# Sheet1.net
KiCad netlist of a schematic drawn in Altium Designer
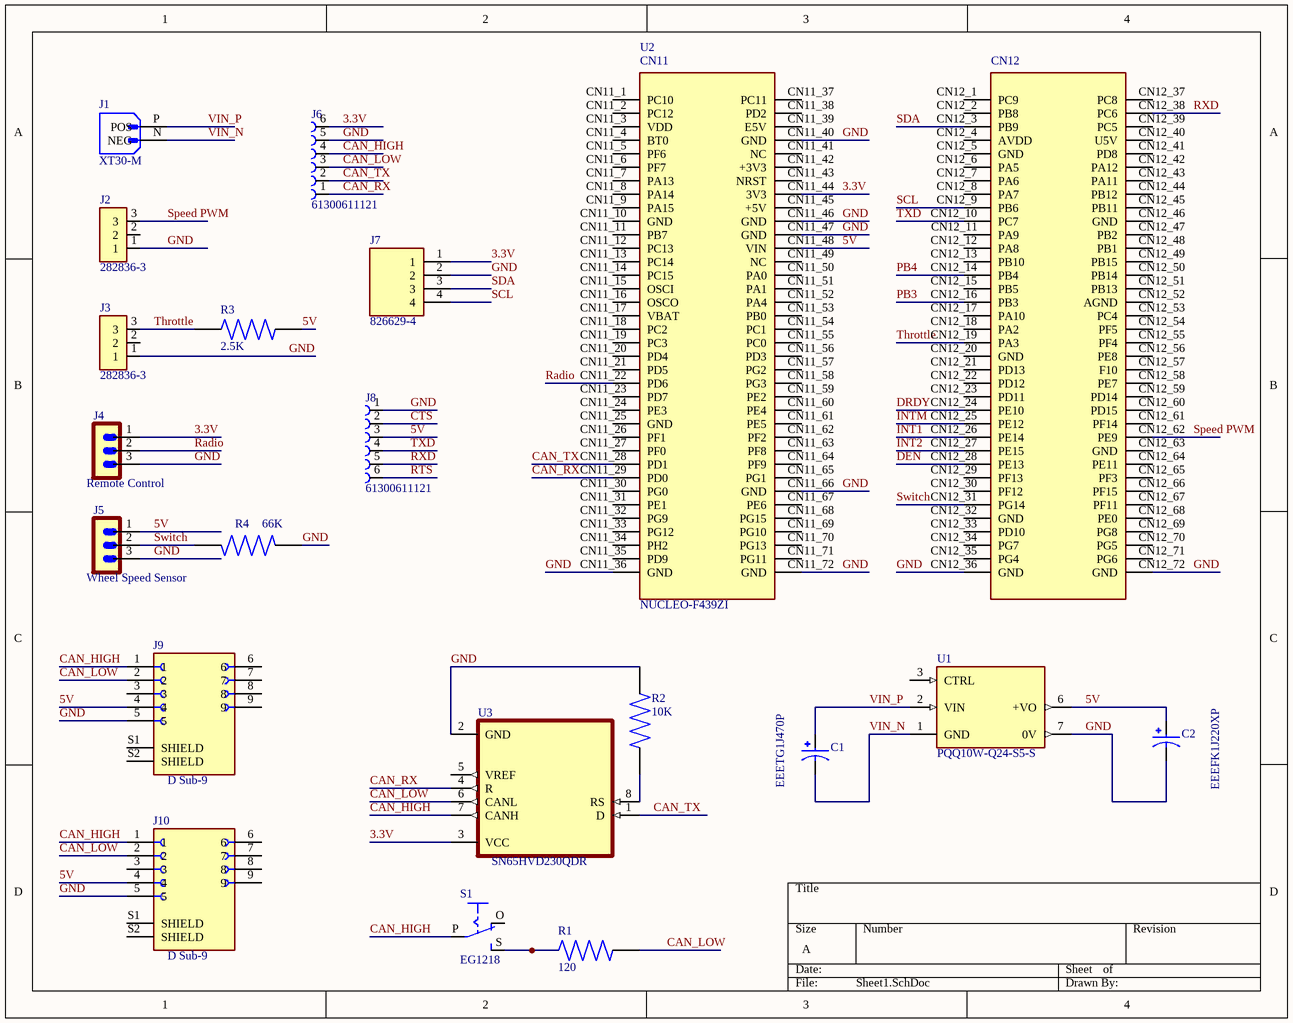
[diagram p0: Sheet1.SchDoc]

(export (version "E")
  (design (tool "Eeschema 10.0.6"))
  (components
    (comp (ref "C1")
      (value "EEETG1J470P")
      (footprint "CAP_EEETG1J470P")
      (description "Cap Aluminum 47uF 63V 20% (10 X 10.2mm) SMD 0.8 Ohm 150mA 2000 hr 125Â°C T/R")
      (fields (field (name "MF") "Panasonic Electronic") (field (name "MP") "EEE-TG1J470P"))
      (libsource (lib "EEETG1J470P") (part "EEETG1J470P"))
    )
    (comp (ref "C2")
      (value "EEEFK1J220XP")
      (footprint "CAP_EEEFK1J220XP")
      (description "22ÂµF 63V Aluminum Electrolytic Capacitors Radial, Can - SMD 2000 Hrs @ 105Â°C")
      (fields (field (name "MP") "EEE-FK1J220XP") (field (name "MF") "Panasonic"))
      (libsource (lib "EEEFK1J220XP") (part "EEEFK1J220XP"))
    )
    (comp (ref "J1")
      (value "XT30-M")
      (footprint "AMASS_XT60-M")
      (description "Plug; DC supply; XT60; male; PIN: 2; for cable; soldered; 30A; 500V")
      (fields (field (name "MP") "XT60-M") (field (name "MF") "AMASS"))
      (libsource (lib "XT30-M") (part "XT30-M"))
    )
    (comp (ref "J2")
      (value "282836-3")
      (footprint "TE_282836-3")
      (description "TERM BLOCK 3POS SIDE ENTRY 5MM")
      (libsource (lib "282836-3") (part "282836-3"))
    )
    (comp (ref "J3")
      (value "282836-3")
      (footprint "TE_282836-3")
      (description "TERM BLOCK 3POS SIDE ENTRY 5MM")
      (libsource (lib "282836-3") (part "282836-3"))
    )
    (comp (ref "J4")
      (value "Remote Control")
      (footprint "B3B-PH-K")
      (description "Connector Header Through Hole 3 position 0.079 (2.00mm)")
      (fields (field (name "MP") "B3B-PH-K") (field (name "MF") "JST"))
      (libsource (lib "B3B-PH-K") (part "B3B-PH-K"))
    )
    (comp (ref "J5")
      (value "Wheel Speed Sensor")
      (footprint "B3B-PH-K")
      (description "Connector Header Through Hole 3 position 0.079 (2.00mm)")
      (fields (field (name "MP") "B3B-PH-K") (field (name "MF") "JST"))
      (libsource (lib "B3B-PH-K") (part "B3B-PH-K"))
    )
    (comp (ref "J6")
      (value "61300611121")
      (footprint "61300611121")
      (description "Connector Header Through Hole 6 position 0.100 (2.54mm)")
      (fields (field (name "MF") "WÃ¼rth Elektronik"))
      (libsource (lib "61300611121") (part "61300611121"))
    )
    (comp (ref "J7")
      (value "826629-4")
      (footprint "TE_826629-4")
      (description "Conn Unshrouded Header HDR 4 POS 2.54mm Solder ST Thru-Hole Automotive Carton")
      (fields (field (name "MF") "TE Connectivity"))
      (libsource (lib "826629-4") (part "826629-4"))
    )
    (comp (ref "J8")
      (value "61300611121")
      (footprint "61300611121")
      (description "Connector Header Through Hole 6 position 0.100 (2.54mm)")
      (fields (field (name "MF") "WÃ¼rth Elektronik"))
      (libsource (lib "") (part "61300611121_1"))
    )
    (comp (ref "J9")
      (value "D Sub-9")
      (footprint "ASSMANN_A-DF_09_A_KG-T2S")
      (description "9 Position D-Sub Receptacle, Female Sockets Connector")
      (fields (field (name "MF") "Assmann WSW") (field (name "MP") "A-DF 09 A/KG-T2S"))
      (libsource (lib "A-DF_09_A_KG-T2S") (part "A-DF_09_A_KG-T2S"))
    )
    (comp (ref "J10")
      (value "D Sub-9")
      (footprint "ASSMANN_A-DF_09_A_KG-T2S")
      (description "9 Position D-Sub Receptacle, Female Sockets Connector")
      (fields (field (name "MF") "Assmann WSW") (field (name "MP") "A-DF 09 A/KG-T2S"))
      (libsource (lib "A-DF_09_A_KG-T2S") (part "A-DF_09_A_KG-T2S"))
    )
    (comp (ref "R1")
      (value "120")
      (footprint "RESC3216X65N")
      (fields (field (name "MP") "KTR18EZPF9530"))
      (libsource (lib "KTR18EZPF9530") (part "KTR18EZPF9530"))
    )
    (comp (ref "R2")
      (value "10K")
      (footprint "RESC3216X65N")
      (fields (field (name "MP") "KTR18EZPF9530"))
      (libsource (lib "KTR18EZPF9530") (part "KTR18EZPF9530"))
    )
    (comp (ref "R3")
      (value "2.5K")
      (footprint "RESC3216X65N")
      (fields (field (name "MP") "KTR18EZPF9530"))
      (libsource (lib "KTR18EZPF9530") (part "KTR18EZPF9530"))
    )
    (comp (ref "R4")
      (value "66K")
      (footprint "RESC3216X65N")
      (fields (field (name "MP") "KTR18EZPF9530"))
      (libsource (lib "KTR18EZPF9530") (part "KTR18EZPF9530"))
    )
    (comp (ref "S1") (value "EG1218") (footprint "EG1218:EG1218") (libsource (lib "EG1218") (part "EG1218")))
    (comp (ref "U1")
      (value "PQQ10W-Q24-S5-S")
      (footprint "CONV_PQQ10W-Q24-S5-S")
      (description "10 W, 4:1 Input Range, Single Regulated Output, SIP8, 1500 Vdc Isolation, Dc-Dc Converter")
      (fields (field (name "MF") "CUI Inc."))
      (libsource (lib "PQQ10W-Q24-S5-S") (part "PQQ10W-Q24-S5-S"))
    )
    (comp (ref "U2")
      (value "NUCLEO-F439ZI")
      (footprint "Nucleo-F439ZI")
      (fields (field (name "MP") "NUCLEO-F429ZI"))
      (libsource (lib "Nucleo-F439ZI") (part "NUCLEO-F439ZI"))
    )
    (comp (ref "U3")
      (value "SN65HVD230QDR")
      (footprint "SOIC127P599X175-8N")
      (description "3.3-V CAN Transceiver with Standby Mode 8-SOIC -40 to 125")
      (fields (field (name "MF") "Texas Instruments"))
      (libsource (lib "SN65HVD230QDR") (part "SN65HVD230QDR"))
    )
  )
  (nets
    (net (code "1") (name "/3.3V") (class "Default")
      (node (ref "J4") (pin "1") (pinfunction "1_1") (pintype "passive"))
      (node (ref "J6") (pin "6") (pinfunction "6_6") (pintype "passive"))
      (node (ref "J7") (pin "1") (pinfunction "1_1") (pintype "passive"))
      (node (ref "U2") (pin "CN11_44") (pinfunction "3V3_CN11_44") (pintype "power_in"))
      (node (ref "U3") (pin "3") (pinfunction "VCC_3") (pintype "power_in"))
    )
    (net (code "2") (name "/5V") (class "Default")
      (node (ref "C2") (pin "1") (pinfunction "1_1") (pintype "passive"))
      (node (ref "J10") (pin "4") (pinfunction "4_4") (pintype "passive"))
      (node (ref "J5") (pin "1") (pinfunction "1_1") (pintype "passive"))
      (node (ref "J8") (pin "3") (pinfunction "3_3") (pintype "passive"))
      (node (ref "J9") (pin "4") (pinfunction "4_4") (pintype "passive"))
      (node (ref "R3") (pin "2") (pinfunction "2_2") (pintype "passive"))
      (node (ref "U1") (pin "6") (pinfunction "+VO_6") (pintype "output"))
      (node (ref "U2") (pin "CN11_48") (pinfunction "VIN_CN11_48") (pintype "power_in"))
    )
    (net (code "3") (name "/CAN_HIGH") (class "Default")
      (node (ref "J10") (pin "1") (pinfunction "1_1") (pintype "passive"))
      (node (ref "J6") (pin "4") (pinfunction "4_4") (pintype "passive"))
      (node (ref "J9") (pin "1") (pinfunction "1_1") (pintype "passive"))
      (node (ref "S1") (pin "P") (pinfunction "P_P") (pintype "passive"))
      (node (ref "U3") (pin "7") (pinfunction "CANH_7") (pintype "output"))
    )
    (net (code "4") (name "/CAN_LOW") (class "Default")
      (node (ref "J10") (pin "2") (pinfunction "2_2") (pintype "passive"))
      (node (ref "J6") (pin "3") (pinfunction "3_3") (pintype "passive"))
      (node (ref "J9") (pin "2") (pinfunction "2_2") (pintype "passive"))
      (node (ref "R1") (pin "2") (pinfunction "2_2") (pintype "passive"))
      (node (ref "U3") (pin "6") (pinfunction "CANL_6") (pintype "output"))
    )
    (net (code "5") (name "/CAN_RX") (class "Default")
      (node (ref "J6") (pin "1") (pinfunction "1_1") (pintype "passive"))
      (node (ref "U2") (pin "CN11_29") (pinfunction "PD0_CN11_29") (pintype "power_in"))
      (node (ref "U3") (pin "4") (pinfunction "R_4") (pintype "output"))
    )
    (net (code "6") (name "/CAN_TX") (class "Default")
      (node (ref "J6") (pin "2") (pinfunction "2_2") (pintype "passive"))
      (node (ref "U2") (pin "CN11_28") (pinfunction "PD1_CN11_28") (pintype "power_in"))
      (node (ref "U3") (pin "1") (pinfunction "D_1") (pintype "input"))
    )
    (net (code "7") (name "/CTS") (class "Default")
      (node (ref "J8") (pin "2") (pinfunction "2_2") (pintype "passive"))
    )
    (net (code "8") (name "/DEN") (class "Default")
      (node (ref "U2") (pin "CN12_28") (pinfunction "PE13_CN12_28") (pintype "power_in"))
    )
    (net (code "9") (name "/DRDY") (class "Default")
      (node (ref "U2") (pin "CN12_24") (pinfunction "PE10_CN12_24") (pintype "power_in"))
    )
    (net (code "10") (name "/GND") (class "Default")
      (node (ref "C2") (pin "2") (pinfunction "2_2") (pintype "passive"))
      (node (ref "J10") (pin "5") (pinfunction "5_5") (pintype "passive"))
      (node (ref "J2") (pin "1") (pinfunction "1_1") (pintype "passive"))
      (node (ref "J3") (pin "1") (pinfunction "1_1") (pintype "passive"))
      (node (ref "J4") (pin "3") (pinfunction "3_3") (pintype "passive"))
      (node (ref "J5") (pin "3") (pinfunction "3_3") (pintype "passive"))
      (node (ref "J6") (pin "5") (pinfunction "5_5") (pintype "passive"))
      (node (ref "J7") (pin "2") (pinfunction "2_2") (pintype "passive"))
      (node (ref "J8") (pin "1") (pinfunction "1_1") (pintype "passive"))
      (node (ref "J9") (pin "5") (pinfunction "5_5") (pintype "passive"))
      (node (ref "R2") (pin "2") (pinfunction "2_2") (pintype "passive"))
      (node (ref "R4") (pin "1") (pinfunction "1_1") (pintype "passive"))
      (node (ref "U1") (pin "7") (pinfunction "0V_7") (pintype "output"))
      (node (ref "U2") (pin "CN11_36") (pinfunction "GND_CN11_36") (pintype "power_in"))
      (node (ref "U2") (pin "CN11_40") (pinfunction "GND_CN11_40") (pintype "power_in"))
      (node (ref "U2") (pin "CN11_46") (pinfunction "GND_CN11_46") (pintype "power_in"))
      (node (ref "U2") (pin "CN11_47") (pinfunction "GND_CN11_47") (pintype "power_in"))
      (node (ref "U2") (pin "CN11_66") (pinfunction "GND_CN11_66") (pintype "power_in"))
      (node (ref "U2") (pin "CN11_72") (pinfunction "GND_CN11_72") (pintype "power_in"))
      (node (ref "U2") (pin "CN12_36") (pinfunction "GND_CN12_36") (pintype "power_in"))
      (node (ref "U2") (pin "CN12_72") (pinfunction "GND_CN12_72") (pintype "power_in"))
      (node (ref "U3") (pin "2") (pinfunction "GND_2") (pintype "power_in"))
    )
    (net (code "11") (name "/INT1") (class "Default")
      (node (ref "U2") (pin "CN12_26") (pinfunction "PE14_CN12_26") (pintype "power_in"))
    )
    (net (code "12") (name "/INT2") (class "Default")
      (node (ref "U2") (pin "CN12_27") (pinfunction "PE15_CN12_27") (pintype "power_in"))
    )
    (net (code "13") (name "/INTM") (class "Default")
      (node (ref "U2") (pin "CN12_25") (pinfunction "PE12_CN12_25") (pintype "power_in"))
    )
    (net (code "14") (name "/PB3") (class "Default")
      (node (ref "U2") (pin "CN12_16") (pinfunction "PB3_CN12_16") (pintype "power_in"))
    )
    (net (code "15") (name "/PB4") (class "Default")
      (node (ref "U2") (pin "CN12_14") (pinfunction "PB4_CN12_14") (pintype "power_in"))
    )
    (net (code "16") (name "/RTS") (class "Default")
      (node (ref "J8") (pin "6") (pinfunction "6_6") (pintype "passive"))
    )
    (net (code "17") (name "/RXD") (class "Default")
      (node (ref "J8") (pin "5") (pinfunction "5_5") (pintype "passive"))
      (node (ref "U2") (pin "CN12_38") (pinfunction "PC6_CN12_38") (pintype "power_in"))
    )
    (net (code "18") (name "/Radio") (class "Default")
      (node (ref "J4") (pin "2") (pinfunction "2_2") (pintype "passive"))
      (node (ref "U2") (pin "CN11_22") (pinfunction "PD6_CN11_22") (pintype "power_in"))
    )
    (net (code "19") (name "/SCL") (class "Default")
      (node (ref "J7") (pin "4") (pinfunction "4_4") (pintype "passive"))
      (node (ref "U2") (pin "CN12_9") (pinfunction "PB6_CN12_9") (pintype "power_in"))
    )
    (net (code "20") (name "/SDA") (class "Default")
      (node (ref "J7") (pin "3") (pinfunction "3_3") (pintype "passive"))
      (node (ref "U2") (pin "CN12_3") (pinfunction "PB9_CN12_3") (pintype "power_in"))
    )
    (net (code "21") (name "/Speed PWM") (class "Default")
      (node (ref "J2") (pin "3") (pinfunction "3_3") (pintype "passive"))
      (node (ref "U2") (pin "CN12_62") (pinfunction "PE9_CN12_62") (pintype "power_in"))
    )
    (net (code "22") (name "/Switch") (class "Default")
      (node (ref "J5") (pin "2") (pinfunction "2_2") (pintype "passive"))
      (node (ref "R4") (pin "2") (pinfunction "2_2") (pintype "passive"))
      (node (ref "U2") (pin "CN12_31") (pinfunction "PG14_CN12_31") (pintype "power_in"))
    )
    (net (code "23") (name "/TXD") (class "Default")
      (node (ref "J8") (pin "4") (pinfunction "4_4") (pintype "passive"))
      (node (ref "U2") (pin "CN12_10") (pinfunction "PC7_CN12_10") (pintype "power_in"))
    )
    (net (code "24") (name "/Throttle") (class "Default")
      (node (ref "J3") (pin "3") (pinfunction "3_3") (pintype "passive"))
      (node (ref "R3") (pin "1") (pinfunction "1_1") (pintype "passive"))
      (node (ref "U2") (pin "CN12_19") (pinfunction "PA3_CN12_19") (pintype "power_in"))
    )
    (net (code "25") (name "/VIN_N") (class "Default")
      (node (ref "C1") (pin "2") (pinfunction "2_2") (pintype "passive"))
      (node (ref "J1") (pin "N") (pinfunction "NEG_N") (pintype "passive"))
      (node (ref "U1") (pin "1") (pinfunction "GND_1") (pintype "power_in"))
    )
    (net (code "26") (name "/VIN_P") (class "Default")
      (node (ref "C1") (pin "1") (pinfunction "1_1") (pintype "passive"))
      (node (ref "J1") (pin "P") (pinfunction "POS_P") (pintype "passive"))
      (node (ref "U1") (pin "2") (pinfunction "VIN_2") (pintype "input"))
    )
    (net (code "27") (name "Net-(R1-Pad1)") (class "Default")
      (node (ref "R1") (pin "1") (pinfunction "1_1") (pintype "passive"))
      (node (ref "S1") (pin "S") (pinfunction "S_S") (pintype "passive"))
    )
    (net (code "28") (name "Net-(U3-RS)") (class "Default")
      (node (ref "R2") (pin "1") (pinfunction "1_1") (pintype "passive"))
      (node (ref "U3") (pin "8") (pinfunction "RS_8") (pintype "input"))
    )
    (net (code "29") (name "unconnected-(J2-Pad2)") (class "Default")
      (node (ref "J2") (pin "2") (pinfunction "2_2") (pintype "passive"))
    )
    (net (code "30") (name "unconnected-(J3-Pad2)") (class "Default")
      (node (ref "J3") (pin "2") (pinfunction "2_2") (pintype "passive"))
    )
    (net (code "31") (name "unconnected-(J9-Pad3)") (class "Default")
      (node (ref "J9") (pin "3") (pinfunction "3_3") (pintype "passive"))
    )
    (net (code "32") (name "unconnected-(J9-Pad6)") (class "Default")
      (node (ref "J9") (pin "6") (pinfunction "6_6") (pintype "passive"))
    )
    (net (code "33") (name "unconnected-(J9-Pad7)") (class "Default")
      (node (ref "J9") (pin "7") (pinfunction "7_7") (pintype "passive"))
    )
    (net (code "34") (name "unconnected-(J9-Pad8)") (class "Default")
      (node (ref "J9") (pin "8") (pinfunction "8_8") (pintype "passive"))
    )
    (net (code "35") (name "unconnected-(J9-Pad9)") (class "Default")
      (node (ref "J9") (pin "9") (pinfunction "9_9") (pintype "passive"))
    )
    (net (code "36") (name "unconnected-(J9-SHIELD-PadS1)") (class "Default")
      (node (ref "J9") (pin "S1") (pinfunction "SHIELD_S1") (pintype "passive"))
    )
    (net (code "37") (name "unconnected-(J9-SHIELD-PadS2)") (class "Default")
      (node (ref "J9") (pin "S2") (pinfunction "SHIELD_S2") (pintype "passive"))
    )
    (net (code "38") (name "unconnected-(J10-Pad3)") (class "Default")
      (node (ref "J10") (pin "3") (pinfunction "3_3") (pintype "passive"))
    )
    (net (code "39") (name "unconnected-(J10-Pad6)") (class "Default")
      (node (ref "J10") (pin "6") (pinfunction "6_6") (pintype "passive"))
    )
    (net (code "40") (name "unconnected-(J10-Pad7)") (class "Default")
      (node (ref "J10") (pin "7") (pinfunction "7_7") (pintype "passive"))
    )
    (net (code "41") (name "unconnected-(J10-Pad8)") (class "Default")
      (node (ref "J10") (pin "8") (pinfunction "8_8") (pintype "passive"))
    )
    (net (code "42") (name "unconnected-(J10-Pad9)") (class "Default")
      (node (ref "J10") (pin "9") (pinfunction "9_9") (pintype "passive"))
    )
    (net (code "43") (name "unconnected-(J10-SHIELD-PadS1)") (class "Default")
      (node (ref "J10") (pin "S1") (pinfunction "SHIELD_S1") (pintype "passive"))
    )
    (net (code "44") (name "unconnected-(J10-SHIELD-PadS2)") (class "Default")
      (node (ref "J10") (pin "S2") (pinfunction "SHIELD_S2") (pintype "passive"))
    )
    (net (code "45") (name "unconnected-(S1-PadO)") (class "Default")
      (node (ref "S1") (pin "O") (pinfunction "O_O") (pintype "passive"))
    )
    (net (code "46") (name "unconnected-(U1-CTRL-Pad3)") (class "Default")
      (node (ref "U1") (pin "3") (pinfunction "CTRL_3") (pintype "input"))
    )
    (net (code "47") (name "unconnected-(U2-+3V3-PadCN11_42)") (class "Default")
      (node (ref "U2") (pin "CN11_42") (pinfunction "+3V3_CN11_42") (pintype "power_in"))
    )
    (net (code "48") (name "unconnected-(U2-+5V-PadCN11_45)") (class "Default")
      (node (ref "U2") (pin "CN11_45") (pinfunction "+5V_CN11_45") (pintype "power_in"))
    )
    (net (code "49") (name "unconnected-(U2-AGND-PadCN12_52)") (class "Default")
      (node (ref "U2") (pin "CN12_52") (pinfunction "AGND_CN12_52") (pintype "power_in"))
    )
    (net (code "50") (name "unconnected-(U2-AVDD-PadCN12_4)") (class "Default")
      (node (ref "U2") (pin "CN12_4") (pinfunction "AVDD_CN12_4") (pintype "power_in"))
    )
    (net (code "51") (name "unconnected-(U2-BT0-PadCN11_4)") (class "Default")
      (node (ref "U2") (pin "CN11_4") (pinfunction "BT0_CN11_4") (pintype "power_in"))
    )
    (net (code "52") (name "unconnected-(U2-E5V-PadCN11_39)") (class "Default")
      (node (ref "U2") (pin "CN11_39") (pinfunction "E5V_CN11_39") (pintype "power_in"))
    )
    (net (code "53") (name "unconnected-(U2-F10-PadCN12_57)") (class "Default")
      (node (ref "U2") (pin "CN12_57") (pinfunction "F10_CN12_57") (pintype "power_in"))
    )
    (net (code "54") (name "unconnected-(U2-GND-PadCN11_10)") (class "Default")
      (node (ref "U2") (pin "CN11_10") (pinfunction "GND_CN11_10") (pintype "power_in"))
    )
    (net (code "55") (name "unconnected-(U2-GND-PadCN11_25)") (class "Default")
      (node (ref "U2") (pin "CN11_25") (pinfunction "GND_CN11_25") (pintype "power_in"))
    )
    (net (code "56") (name "unconnected-(U2-GND-PadCN12_5)") (class "Default")
      (node (ref "U2") (pin "CN12_5") (pinfunction "GND_CN12_5") (pintype "power_in"))
    )
    (net (code "57") (name "unconnected-(U2-GND-PadCN12_20)") (class "Default")
      (node (ref "U2") (pin "CN12_20") (pinfunction "GND_CN12_20") (pintype "power_in"))
    )
    (net (code "58") (name "unconnected-(U2-GND-PadCN12_32)") (class "Default")
      (node (ref "U2") (pin "CN12_32") (pinfunction "GND_CN12_32") (pintype "power_in"))
    )
    (net (code "59") (name "unconnected-(U2-GND-PadCN12_46)") (class "Default")
      (node (ref "U2") (pin "CN12_46") (pinfunction "GND_CN12_46") (pintype "power_in"))
    )
    (net (code "60") (name "unconnected-(U2-GND-PadCN12_63)") (class "Default")
      (node (ref "U2") (pin "CN12_63") (pinfunction "GND_CN12_63") (pintype "power_in"))
    )
    (net (code "61") (name "unconnected-(U2-NC-PadCN11_41)") (class "Default")
      (node (ref "U2") (pin "CN11_41") (pinfunction "NC_CN11_41") (pintype "power_in"))
    )
    (net (code "62") (name "unconnected-(U2-NC-PadCN11_49)") (class "Default")
      (node (ref "U2") (pin "CN11_49") (pinfunction "NC_CN11_49") (pintype "power_in"))
    )
    (net (code "63") (name "unconnected-(U2-NRST-PadCN11_43)") (class "Default")
      (node (ref "U2") (pin "CN11_43") (pinfunction "NRST_CN11_43") (pintype "power_in"))
    )
    (net (code "64") (name "unconnected-(U2-OSCI-PadCN11_15)") (class "Default")
      (node (ref "U2") (pin "CN11_15") (pinfunction "OSCI_CN11_15") (pintype "power_in"))
    )
    (net (code "65") (name "unconnected-(U2-OSCO-PadCN11_16)") (class "Default")
      (node (ref "U2") (pin "CN11_16") (pinfunction "OSCO_CN11_16") (pintype "power_in"))
    )
    (net (code "66") (name "unconnected-(U2-PA0-PadCN11_50)") (class "Default")
      (node (ref "U2") (pin "CN11_50") (pinfunction "PA0_CN11_50") (pintype "power_in"))
    )
    (net (code "67") (name "unconnected-(U2-PA1-PadCN11_51)") (class "Default")
      (node (ref "U2") (pin "CN11_51") (pinfunction "PA1_CN11_51") (pintype "power_in"))
    )
    (net (code "68") (name "unconnected-(U2-PA2-PadCN12_18)") (class "Default")
      (node (ref "U2") (pin "CN12_18") (pinfunction "PA2_CN12_18") (pintype "power_in"))
    )
    (net (code "69") (name "unconnected-(U2-PA4-PadCN11_52)") (class "Default")
      (node (ref "U2") (pin "CN11_52") (pinfunction "PA4_CN11_52") (pintype "power_in"))
    )
    (net (code "70") (name "unconnected-(U2-PA5-PadCN12_6)") (class "Default")
      (node (ref "U2") (pin "CN12_6") (pinfunction "PA5_CN12_6") (pintype "power_in"))
    )
    (net (code "71") (name "unconnected-(U2-PA6-PadCN12_7)") (class "Default")
      (node (ref "U2") (pin "CN12_7") (pinfunction "PA6_CN12_7") (pintype "power_in"))
    )
    (net (code "72") (name "unconnected-(U2-PA7-PadCN12_8)") (class "Default")
      (node (ref "U2") (pin "CN12_8") (pinfunction "PA7_CN12_8") (pintype "power_in"))
    )
    (net (code "73") (name "unconnected-(U2-PA8-PadCN12_12)") (class "Default")
      (node (ref "U2") (pin "CN12_12") (pinfunction "PA8_CN12_12") (pintype "power_in"))
    )
    (net (code "74") (name "unconnected-(U2-PA9-PadCN12_11)") (class "Default")
      (node (ref "U2") (pin "CN12_11") (pinfunction "PA9_CN12_11") (pintype "power_in"))
    )
    (net (code "75") (name "unconnected-(U2-PA10-PadCN12_17)") (class "Default")
      (node (ref "U2") (pin "CN12_17") (pinfunction "PA10_CN12_17") (pintype "power_in"))
    )
    (net (code "76") (name "unconnected-(U2-PA11-PadCN12_43)") (class "Default")
      (node (ref "U2") (pin "CN12_43") (pinfunction "PA11_CN12_43") (pintype "power_in"))
    )
    (net (code "77") (name "unconnected-(U2-PA12-PadCN12_42)") (class "Default")
      (node (ref "U2") (pin "CN12_42") (pinfunction "PA12_CN12_42") (pintype "power_in"))
    )
    (net (code "78") (name "unconnected-(U2-PA13-PadCN11_7)") (class "Default")
      (node (ref "U2") (pin "CN11_7") (pinfunction "PA13_CN11_7") (pintype "power_in"))
    )
    (net (code "79") (name "unconnected-(U2-PA14-PadCN11_8)") (class "Default")
      (node (ref "U2") (pin "CN11_8") (pinfunction "PA14_CN11_8") (pintype "power_in"))
    )
    (net (code "80") (name "unconnected-(U2-PA15-PadCN11_9)") (class "Default")
      (node (ref "U2") (pin "CN11_9") (pinfunction "PA15_CN11_9") (pintype "power_in"))
    )
    (net (code "81") (name "unconnected-(U2-PB0-PadCN11_53)") (class "Default")
      (node (ref "U2") (pin "CN11_53") (pinfunction "PB0_CN11_53") (pintype "power_in"))
    )
    (net (code "82") (name "unconnected-(U2-PB1-PadCN12_48)") (class "Default")
      (node (ref "U2") (pin "CN12_48") (pinfunction "PB1_CN12_48") (pintype "power_in"))
    )
    (net (code "83") (name "unconnected-(U2-PB2-PadCN12_47)") (class "Default")
      (node (ref "U2") (pin "CN12_47") (pinfunction "PB2_CN12_47") (pintype "power_in"))
    )
    (net (code "84") (name "unconnected-(U2-PB5-PadCN12_15)") (class "Default")
      (node (ref "U2") (pin "CN12_15") (pinfunction "PB5_CN12_15") (pintype "power_in"))
    )
    (net (code "85") (name "unconnected-(U2-PB7-PadCN11_11)") (class "Default")
      (node (ref "U2") (pin "CN11_11") (pinfunction "PB7_CN11_11") (pintype "power_in"))
    )
    (net (code "86") (name "unconnected-(U2-PB8-PadCN12_2)") (class "Default")
      (node (ref "U2") (pin "CN12_2") (pinfunction "PB8_CN12_2") (pintype "power_in"))
    )
    (net (code "87") (name "unconnected-(U2-PB10-PadCN12_13)") (class "Default")
      (node (ref "U2") (pin "CN12_13") (pinfunction "PB10_CN12_13") (pintype "power_in"))
    )
    (net (code "88") (name "unconnected-(U2-PB11-PadCN12_45)") (class "Default")
      (node (ref "U2") (pin "CN12_45") (pinfunction "PB11_CN12_45") (pintype "power_in"))
    )
    (net (code "89") (name "unconnected-(U2-PB12-PadCN12_44)") (class "Default")
      (node (ref "U2") (pin "CN12_44") (pinfunction "PB12_CN12_44") (pintype "power_in"))
    )
    (net (code "90") (name "unconnected-(U2-PB13-PadCN12_51)") (class "Default")
      (node (ref "U2") (pin "CN12_51") (pinfunction "PB13_CN12_51") (pintype "power_in"))
    )
    (net (code "91") (name "unconnected-(U2-PB14-PadCN12_50)") (class "Default")
      (node (ref "U2") (pin "CN12_50") (pinfunction "PB14_CN12_50") (pintype "power_in"))
    )
    (net (code "92") (name "unconnected-(U2-PB15-PadCN12_49)") (class "Default")
      (node (ref "U2") (pin "CN12_49") (pinfunction "PB15_CN12_49") (pintype "power_in"))
    )
    (net (code "93") (name "unconnected-(U2-PC0-PadCN11_55)") (class "Default")
      (node (ref "U2") (pin "CN11_55") (pinfunction "PC0_CN11_55") (pintype "power_in"))
    )
    (net (code "94") (name "unconnected-(U2-PC1-PadCN11_54)") (class "Default")
      (node (ref "U2") (pin "CN11_54") (pinfunction "PC1_CN11_54") (pintype "power_in"))
    )
    (net (code "95") (name "unconnected-(U2-PC2-PadCN11_18)") (class "Default")
      (node (ref "U2") (pin "CN11_18") (pinfunction "PC2_CN11_18") (pintype "power_in"))
    )
    (net (code "96") (name "unconnected-(U2-PC3-PadCN11_19)") (class "Default")
      (node (ref "U2") (pin "CN11_19") (pinfunction "PC3_CN11_19") (pintype "power_in"))
    )
    (net (code "97") (name "unconnected-(U2-PC4-PadCN12_53)") (class "Default")
      (node (ref "U2") (pin "CN12_53") (pinfunction "PC4_CN12_53") (pintype "power_in"))
    )
    (net (code "98") (name "unconnected-(U2-PC5-PadCN12_39)") (class "Default")
      (node (ref "U2") (pin "CN12_39") (pinfunction "PC5_CN12_39") (pintype "power_in"))
    )
    (net (code "99") (name "unconnected-(U2-PC8-PadCN12_37)") (class "Default")
      (node (ref "U2") (pin "CN12_37") (pinfunction "PC8_CN12_37") (pintype "power_in"))
    )
    (net (code "100") (name "unconnected-(U2-PC9-PadCN12_1)") (class "Default")
      (node (ref "U2") (pin "CN12_1") (pinfunction "PC9_CN12_1") (pintype "power_in"))
    )
    (net (code "101") (name "unconnected-(U2-PC10-PadCN11_1)") (class "Default")
      (node (ref "U2") (pin "CN11_1") (pinfunction "PC10_CN11_1") (pintype "power_in"))
    )
    (net (code "102") (name "unconnected-(U2-PC11-PadCN11_37)") (class "Default")
      (node (ref "U2") (pin "CN11_37") (pinfunction "PC11_CN11_37") (pintype "power_in"))
    )
    (net (code "103") (name "unconnected-(U2-PC12-PadCN11_2)") (class "Default")
      (node (ref "U2") (pin "CN11_2") (pinfunction "PC12_CN11_2") (pintype "power_in"))
    )
    (net (code "104") (name "unconnected-(U2-PC13-PadCN11_12)") (class "Default")
      (node (ref "U2") (pin "CN11_12") (pinfunction "PC13_CN11_12") (pintype "power_in"))
    )
    (net (code "105") (name "unconnected-(U2-PC14-PadCN11_13)") (class "Default")
      (node (ref "U2") (pin "CN11_13") (pinfunction "PC14_CN11_13") (pintype "power_in"))
    )
    (net (code "106") (name "unconnected-(U2-PC15-PadCN11_14)") (class "Default")
      (node (ref "U2") (pin "CN11_14") (pinfunction "PC15_CN11_14") (pintype "power_in"))
    )
    (net (code "107") (name "unconnected-(U2-PD2-PadCN11_38)") (class "Default")
      (node (ref "U2") (pin "CN11_38") (pinfunction "PD2_CN11_38") (pintype "power_in"))
    )
    (net (code "108") (name "unconnected-(U2-PD3-PadCN11_56)") (class "Default")
      (node (ref "U2") (pin "CN11_56") (pinfunction "PD3_CN11_56") (pintype "power_in"))
    )
    (net (code "109") (name "unconnected-(U2-PD4-PadCN11_20)") (class "Default")
      (node (ref "U2") (pin "CN11_20") (pinfunction "PD4_CN11_20") (pintype "power_in"))
    )
    (net (code "110") (name "unconnected-(U2-PD5-PadCN11_21)") (class "Default")
      (node (ref "U2") (pin "CN11_21") (pinfunction "PD5_CN11_21") (pintype "power_in"))
    )
    (net (code "111") (name "unconnected-(U2-PD7-PadCN11_23)") (class "Default")
      (node (ref "U2") (pin "CN11_23") (pinfunction "PD7_CN11_23") (pintype "power_in"))
    )
    (net (code "112") (name "unconnected-(U2-PD8-PadCN12_41)") (class "Default")
      (node (ref "U2") (pin "CN12_41") (pinfunction "PD8_CN12_41") (pintype "power_in"))
    )
    (net (code "113") (name "unconnected-(U2-PD9-PadCN11_35)") (class "Default")
      (node (ref "U2") (pin "CN11_35") (pinfunction "PD9_CN11_35") (pintype "power_in"))
    )
    (net (code "114") (name "unconnected-(U2-PD10-PadCN12_33)") (class "Default")
      (node (ref "U2") (pin "CN12_33") (pinfunction "PD10_CN12_33") (pintype "power_in"))
    )
    (net (code "115") (name "unconnected-(U2-PD11-PadCN12_23)") (class "Default")
      (node (ref "U2") (pin "CN12_23") (pinfunction "PD11_CN12_23") (pintype "power_in"))
    )
    (net (code "116") (name "unconnected-(U2-PD12-PadCN12_22)") (class "Default")
      (node (ref "U2") (pin "CN12_22") (pinfunction "PD12_CN12_22") (pintype "power_in"))
    )
    (net (code "117") (name "unconnected-(U2-PD13-PadCN12_21)") (class "Default")
      (node (ref "U2") (pin "CN12_21") (pinfunction "PD13_CN12_21") (pintype "power_in"))
    )
    (net (code "118") (name "unconnected-(U2-PD14-PadCN12_59)") (class "Default")
      (node (ref "U2") (pin "CN12_59") (pinfunction "PD14_CN12_59") (pintype "power_in"))
    )
    (net (code "119") (name "unconnected-(U2-PD15-PadCN12_60)") (class "Default")
      (node (ref "U2") (pin "CN12_60") (pinfunction "PD15_CN12_60") (pintype "power_in"))
    )
    (net (code "120") (name "unconnected-(U2-PE0-PadCN12_68)") (class "Default")
      (node (ref "U2") (pin "CN12_68") (pinfunction "PE0_CN12_68") (pintype "power_in"))
    )
    (net (code "121") (name "unconnected-(U2-PE1-PadCN11_31)") (class "Default")
      (node (ref "U2") (pin "CN11_31") (pinfunction "PE1_CN11_31") (pintype "power_in"))
    )
    (net (code "122") (name "unconnected-(U2-PE2-PadCN11_59)") (class "Default")
      (node (ref "U2") (pin "CN11_59") (pinfunction "PE2_CN11_59") (pintype "power_in"))
    )
    (net (code "123") (name "unconnected-(U2-PE3-PadCN11_24)") (class "Default")
      (node (ref "U2") (pin "CN11_24") (pinfunction "PE3_CN11_24") (pintype "power_in"))
    )
    (net (code "124") (name "unconnected-(U2-PE4-PadCN11_60)") (class "Default")
      (node (ref "U2") (pin "CN11_60") (pinfunction "PE4_CN11_60") (pintype "power_in"))
    )
    (net (code "125") (name "unconnected-(U2-PE5-PadCN11_61)") (class "Default")
      (node (ref "U2") (pin "CN11_61") (pinfunction "PE5_CN11_61") (pintype "power_in"))
    )
    (net (code "126") (name "unconnected-(U2-PE6-PadCN11_67)") (class "Default")
      (node (ref "U2") (pin "CN11_67") (pinfunction "PE6_CN11_67") (pintype "power_in"))
    )
    (net (code "127") (name "unconnected-(U2-PE7-PadCN12_58)") (class "Default")
      (node (ref "U2") (pin "CN12_58") (pinfunction "PE7_CN12_58") (pintype "power_in"))
    )
    (net (code "128") (name "unconnected-(U2-PE8-PadCN12_56)") (class "Default")
      (node (ref "U2") (pin "CN12_56") (pinfunction "PE8_CN12_56") (pintype "power_in"))
    )
    (net (code "129") (name "unconnected-(U2-PE11-PadCN12_64)") (class "Default")
      (node (ref "U2") (pin "CN12_64") (pinfunction "PE11_CN12_64") (pintype "power_in"))
    )
    (net (code "130") (name "unconnected-(U2-PF0-PadCN11_27)") (class "Default")
      (node (ref "U2") (pin "CN11_27") (pinfunction "PF0_CN11_27") (pintype "power_in"))
    )
    (net (code "131") (name "unconnected-(U2-PF1-PadCN11_26)") (class "Default")
      (node (ref "U2") (pin "CN11_26") (pinfunction "PF1_CN11_26") (pintype "power_in"))
    )
    (net (code "132") (name "unconnected-(U2-PF2-PadCN11_62)") (class "Default")
      (node (ref "U2") (pin "CN11_62") (pinfunction "PF2_CN11_62") (pintype "power_in"))
    )
    (net (code "133") (name "unconnected-(U2-PF3-PadCN12_65)") (class "Default")
      (node (ref "U2") (pin "CN12_65") (pinfunction "PF3_CN12_65") (pintype "power_in"))
    )
    (net (code "134") (name "unconnected-(U2-PF4-PadCN12_55)") (class "Default")
      (node (ref "U2") (pin "CN12_55") (pinfunction "PF4_CN12_55") (pintype "power_in"))
    )
    (net (code "135") (name "unconnected-(U2-PF5-PadCN12_54)") (class "Default")
      (node (ref "U2") (pin "CN12_54") (pinfunction "PF5_CN12_54") (pintype "power_in"))
    )
    (net (code "136") (name "unconnected-(U2-PF6-PadCN11_5)") (class "Default")
      (node (ref "U2") (pin "CN11_5") (pinfunction "PF6_CN11_5") (pintype "power_in"))
    )
    (net (code "137") (name "unconnected-(U2-PF7-PadCN11_6)") (class "Default")
      (node (ref "U2") (pin "CN11_6") (pinfunction "PF7_CN11_6") (pintype "power_in"))
    )
    (net (code "138") (name "unconnected-(U2-PF8-PadCN11_63)") (class "Default")
      (node (ref "U2") (pin "CN11_63") (pinfunction "PF8_CN11_63") (pintype "power_in"))
    )
    (net (code "139") (name "unconnected-(U2-PF9-PadCN11_64)") (class "Default")
      (node (ref "U2") (pin "CN11_64") (pinfunction "PF9_CN11_64") (pintype "power_in"))
    )
    (net (code "140") (name "unconnected-(U2-PF11-PadCN12_67)") (class "Default")
      (node (ref "U2") (pin "CN12_67") (pinfunction "PF11_CN12_67") (pintype "power_in"))
    )
    (net (code "141") (name "unconnected-(U2-PF12-PadCN12_30)") (class "Default")
      (node (ref "U2") (pin "CN12_30") (pinfunction "PF12_CN12_30") (pintype "power_in"))
    )
    (net (code "142") (name "unconnected-(U2-PF13-PadCN12_29)") (class "Default")
      (node (ref "U2") (pin "CN12_29") (pinfunction "PF13_CN12_29") (pintype "power_in"))
    )
    (net (code "143") (name "unconnected-(U2-PF14-PadCN12_61)") (class "Default")
      (node (ref "U2") (pin "CN12_61") (pinfunction "PF14_CN12_61") (pintype "power_in"))
    )
    (net (code "144") (name "unconnected-(U2-PF15-PadCN12_66)") (class "Default")
      (node (ref "U2") (pin "CN12_66") (pinfunction "PF15_CN12_66") (pintype "power_in"))
    )
    (net (code "145") (name "unconnected-(U2-PG0-PadCN11_30)") (class "Default")
      (node (ref "U2") (pin "CN11_30") (pinfunction "PG0_CN11_30") (pintype "power_in"))
    )
    (net (code "146") (name "unconnected-(U2-PG1-PadCN11_65)") (class "Default")
      (node (ref "U2") (pin "CN11_65") (pinfunction "PG1_CN11_65") (pintype "power_in"))
    )
    (net (code "147") (name "unconnected-(U2-PG2-PadCN11_57)") (class "Default")
      (node (ref "U2") (pin "CN11_57") (pinfunction "PG2_CN11_57") (pintype "power_in"))
    )
    (net (code "148") (name "unconnected-(U2-PG3-PadCN11_58)") (class "Default")
      (node (ref "U2") (pin "CN11_58") (pinfunction "PG3_CN11_58") (pintype "power_in"))
    )
    (net (code "149") (name "unconnected-(U2-PG4-PadCN12_35)") (class "Default")
      (node (ref "U2") (pin "CN12_35") (pinfunction "PG4_CN12_35") (pintype "power_in"))
    )
    (net (code "150") (name "unconnected-(U2-PG5-PadCN12_70)") (class "Default")
      (node (ref "U2") (pin "CN12_70") (pinfunction "PG5_CN12_70") (pintype "power_in"))
    )
    (net (code "151") (name "unconnected-(U2-PG6-PadCN12_71)") (class "Default")
      (node (ref "U2") (pin "CN12_71") (pinfunction "PG6_CN12_71") (pintype "power_in"))
    )
    (net (code "152") (name "unconnected-(U2-PG7-PadCN12_34)") (class "Default")
      (node (ref "U2") (pin "CN12_34") (pinfunction "PG7_CN12_34") (pintype "power_in"))
    )
    (net (code "153") (name "unconnected-(U2-PG8-PadCN12_69)") (class "Default")
      (node (ref "U2") (pin "CN12_69") (pinfunction "PG8_CN12_69") (pintype "power_in"))
    )
    (net (code "154") (name "unconnected-(U2-PG9-PadCN11_32)") (class "Default")
      (node (ref "U2") (pin "CN11_32") (pinfunction "PG9_CN11_32") (pintype "power_in"))
    )
    (net (code "155") (name "unconnected-(U2-PG10-PadCN11_69)") (class "Default")
      (node (ref "U2") (pin "CN11_69") (pinfunction "PG10_CN11_69") (pintype "power_in"))
    )
    (net (code "156") (name "unconnected-(U2-PG11-PadCN11_71)") (class "Default")
      (node (ref "U2") (pin "CN11_71") (pinfunction "PG11_CN11_71") (pintype "power_in"))
    )
    (net (code "157") (name "unconnected-(U2-PG12-PadCN11_33)") (class "Default")
      (node (ref "U2") (pin "CN11_33") (pinfunction "PG12_CN11_33") (pintype "power_in"))
    )
    (net (code "158") (name "unconnected-(U2-PG13-PadCN11_70)") (class "Default")
      (node (ref "U2") (pin "CN11_70") (pinfunction "PG13_CN11_70") (pintype "power_in"))
    )
    (net (code "159") (name "unconnected-(U2-PG15-PadCN11_68)") (class "Default")
      (node (ref "U2") (pin "CN11_68") (pinfunction "PG15_CN11_68") (pintype "power_in"))
    )
    (net (code "160") (name "unconnected-(U2-PH2-PadCN11_34)") (class "Default")
      (node (ref "U2") (pin "CN11_34") (pinfunction "PH2_CN11_34") (pintype "power_in"))
    )
    (net (code "161") (name "unconnected-(U2-U5V-PadCN12_40)") (class "Default")
      (node (ref "U2") (pin "CN12_40") (pinfunction "U5V_CN12_40") (pintype "power_in"))
    )
    (net (code "162") (name "unconnected-(U2-VBAT-PadCN11_17)") (class "Default")
      (node (ref "U2") (pin "CN11_17") (pinfunction "VBAT_CN11_17") (pintype "power_in"))
    )
    (net (code "163") (name "unconnected-(U2-VDD-PadCN11_3)") (class "Default")
      (node (ref "U2") (pin "CN11_3") (pinfunction "VDD_CN11_3") (pintype "power_in"))
    )
    (net (code "164") (name "unconnected-(U3-VREF-Pad5)") (class "Default")
      (node (ref "U3") (pin "5") (pinfunction "VREF_5") (pintype "output"))
    )
  )
)
